# rpi_breakout.net
KiCad netlist of a schematic drawn in EAGLE
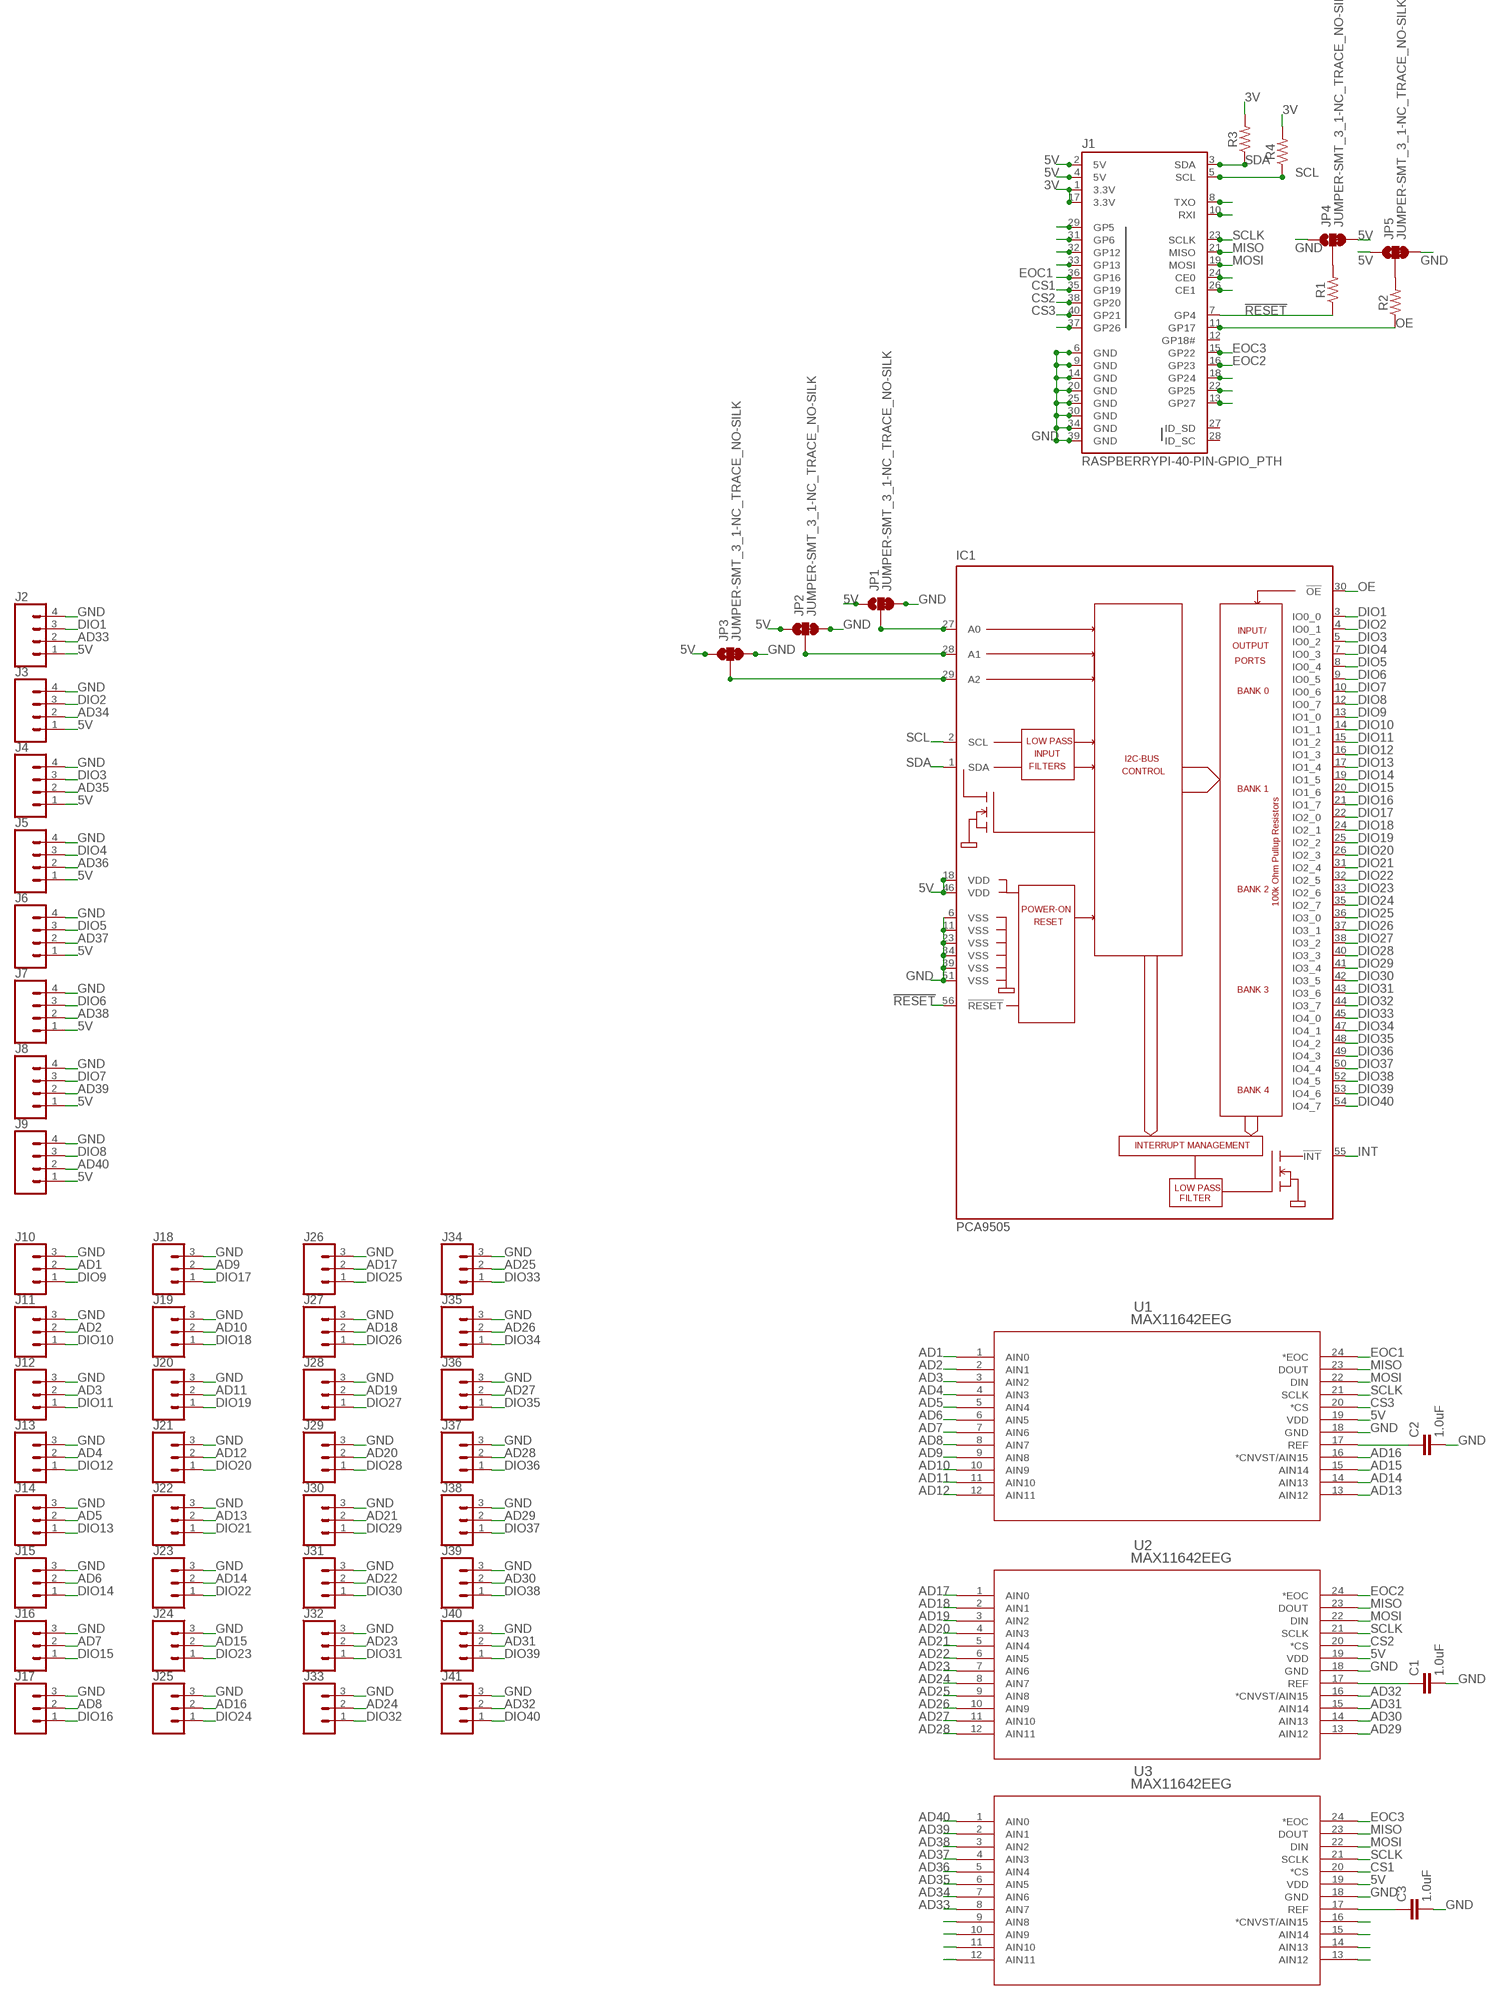
[diagram p0: schematic, sheet 1]

(export (version "E")
  (design (tool "Eeschema 10.0.6"))
  (components
    (comp (ref "C1")
      (value "1.0uF")
      (footprint "eagle-import:0805")
      (libsource (lib "eagle-import") (part "1.0UF-0805-25V-10%"))
    )
    (comp (ref "C2")
      (value "1.0uF")
      (footprint "eagle-import:0805")
      (libsource (lib "eagle-import") (part "1.0UF-0805-25V-10%"))
    )
    (comp (ref "C3")
      (value "1.0uF")
      (footprint "eagle-import:0805")
      (libsource (lib "eagle-import") (part "1.0UF-0805-25V-10%"))
    )
    (comp (ref "IC1")
      (value "PCA9505")
      (footprint "eagle-import:TSSOP56-6")
      (fields (field (name "MPN") "PCA9505DGG,118"))
      (libsource (lib "eagle-import") (part "PCA9505"))
    )
    (comp (ref "J1")
      (value "RASPBERRYPI-40-PIN-GPIO_PTH")
      (footprint "eagle-import:2X20_SHROUDED")
      (libsource (lib "eagle-import") (part "RASPBERRYPI-40-PIN-GPIO_PTH"))
    )
    (comp (ref "J2")
      (value "CONN_04JST-PTH")
      (footprint "eagle-import:JST-4-PTH")
      (libsource (lib "eagle-import") (part "CONN_04JST-PTH"))
    )
    (comp (ref "J3")
      (value "CONN_04JST-PTH")
      (footprint "eagle-import:JST-4-PTH")
      (libsource (lib "eagle-import") (part "CONN_04JST-PTH"))
    )
    (comp (ref "J4")
      (value "CONN_04JST-PTH")
      (footprint "eagle-import:JST-4-PTH")
      (libsource (lib "eagle-import") (part "CONN_04JST-PTH"))
    )
    (comp (ref "J5")
      (value "CONN_04JST-PTH")
      (footprint "eagle-import:JST-4-PTH")
      (libsource (lib "eagle-import") (part "CONN_04JST-PTH"))
    )
    (comp (ref "J6")
      (value "CONN_04JST-PTH")
      (footprint "eagle-import:JST-4-PTH")
      (libsource (lib "eagle-import") (part "CONN_04JST-PTH"))
    )
    (comp (ref "J7")
      (value "CONN_04JST-PTH")
      (footprint "eagle-import:JST-4-PTH")
      (libsource (lib "eagle-import") (part "CONN_04JST-PTH"))
    )
    (comp (ref "J8")
      (value "CONN_04JST-PTH")
      (footprint "eagle-import:JST-4-PTH")
      (libsource (lib "eagle-import") (part "CONN_04JST-PTH"))
    )
    (comp (ref "J9")
      (value "CONN_04JST-PTH")
      (footprint "eagle-import:JST-4-PTH")
      (libsource (lib "eagle-import") (part "CONN_04JST-PTH"))
    )
    (comp (ref "J10")
      (value "CONN_03JST-PTH")
      (footprint "eagle-import:JST-3-PTH")
      (libsource (lib "eagle-import") (part "CONN_03JST-PTH"))
    )
    (comp (ref "J11")
      (value "CONN_03JST-PTH")
      (footprint "eagle-import:JST-3-PTH")
      (libsource (lib "eagle-import") (part "CONN_03JST-PTH"))
    )
    (comp (ref "J12")
      (value "CONN_03JST-PTH")
      (footprint "eagle-import:JST-3-PTH")
      (libsource (lib "eagle-import") (part "CONN_03JST-PTH"))
    )
    (comp (ref "J13")
      (value "CONN_03JST-PTH")
      (footprint "eagle-import:JST-3-PTH")
      (libsource (lib "eagle-import") (part "CONN_03JST-PTH"))
    )
    (comp (ref "J14")
      (value "CONN_03JST-PTH")
      (footprint "eagle-import:JST-3-PTH")
      (libsource (lib "eagle-import") (part "CONN_03JST-PTH"))
    )
    (comp (ref "J15")
      (value "CONN_03JST-PTH")
      (footprint "eagle-import:JST-3-PTH")
      (libsource (lib "eagle-import") (part "CONN_03JST-PTH"))
    )
    (comp (ref "J16")
      (value "CONN_03JST-PTH")
      (footprint "eagle-import:JST-3-PTH")
      (libsource (lib "eagle-import") (part "CONN_03JST-PTH"))
    )
    (comp (ref "J17")
      (value "CONN_03JST-PTH")
      (footprint "eagle-import:JST-3-PTH")
      (libsource (lib "eagle-import") (part "CONN_03JST-PTH"))
    )
    (comp (ref "J18")
      (value "CONN_03JST-PTH")
      (footprint "eagle-import:JST-3-PTH")
      (libsource (lib "eagle-import") (part "CONN_03JST-PTH"))
    )
    (comp (ref "J19")
      (value "CONN_03JST-PTH")
      (footprint "eagle-import:JST-3-PTH")
      (libsource (lib "eagle-import") (part "CONN_03JST-PTH"))
    )
    (comp (ref "J20")
      (value "CONN_03JST-PTH")
      (footprint "eagle-import:JST-3-PTH")
      (libsource (lib "eagle-import") (part "CONN_03JST-PTH"))
    )
    (comp (ref "J21")
      (value "CONN_03JST-PTH")
      (footprint "eagle-import:JST-3-PTH")
      (libsource (lib "eagle-import") (part "CONN_03JST-PTH"))
    )
    (comp (ref "J22")
      (value "CONN_03JST-PTH")
      (footprint "eagle-import:JST-3-PTH")
      (libsource (lib "eagle-import") (part "CONN_03JST-PTH"))
    )
    (comp (ref "J23")
      (value "CONN_03JST-PTH")
      (footprint "eagle-import:JST-3-PTH")
      (libsource (lib "eagle-import") (part "CONN_03JST-PTH"))
    )
    (comp (ref "J24")
      (value "CONN_03JST-PTH")
      (footprint "eagle-import:JST-3-PTH")
      (libsource (lib "eagle-import") (part "CONN_03JST-PTH"))
    )
    (comp (ref "J25")
      (value "CONN_03JST-PTH")
      (footprint "eagle-import:JST-3-PTH")
      (libsource (lib "eagle-import") (part "CONN_03JST-PTH"))
    )
    (comp (ref "J26")
      (value "CONN_03JST-PTH")
      (footprint "eagle-import:JST-3-PTH")
      (libsource (lib "eagle-import") (part "CONN_03JST-PTH"))
    )
    (comp (ref "J27")
      (value "CONN_03JST-PTH")
      (footprint "eagle-import:JST-3-PTH")
      (libsource (lib "eagle-import") (part "CONN_03JST-PTH"))
    )
    (comp (ref "J28")
      (value "CONN_03JST-PTH")
      (footprint "eagle-import:JST-3-PTH")
      (libsource (lib "eagle-import") (part "CONN_03JST-PTH"))
    )
    (comp (ref "J29")
      (value "CONN_03JST-PTH")
      (footprint "eagle-import:JST-3-PTH")
      (libsource (lib "eagle-import") (part "CONN_03JST-PTH"))
    )
    (comp (ref "J30")
      (value "CONN_03JST-PTH")
      (footprint "eagle-import:JST-3-PTH")
      (libsource (lib "eagle-import") (part "CONN_03JST-PTH"))
    )
    (comp (ref "J31")
      (value "CONN_03JST-PTH")
      (footprint "eagle-import:JST-3-PTH")
      (libsource (lib "eagle-import") (part "CONN_03JST-PTH"))
    )
    (comp (ref "J32")
      (value "CONN_03JST-PTH")
      (footprint "eagle-import:JST-3-PTH")
      (libsource (lib "eagle-import") (part "CONN_03JST-PTH"))
    )
    (comp (ref "J33")
      (value "CONN_03JST-PTH")
      (footprint "eagle-import:JST-3-PTH")
      (libsource (lib "eagle-import") (part "CONN_03JST-PTH"))
    )
    (comp (ref "J34")
      (value "CONN_03JST-PTH")
      (footprint "eagle-import:JST-3-PTH")
      (libsource (lib "eagle-import") (part "CONN_03JST-PTH"))
    )
    (comp (ref "J35")
      (value "CONN_03JST-PTH")
      (footprint "eagle-import:JST-3-PTH")
      (libsource (lib "eagle-import") (part "CONN_03JST-PTH"))
    )
    (comp (ref "J36")
      (value "CONN_03JST-PTH")
      (footprint "eagle-import:JST-3-PTH")
      (libsource (lib "eagle-import") (part "CONN_03JST-PTH"))
    )
    (comp (ref "J37")
      (value "CONN_03JST-PTH")
      (footprint "eagle-import:JST-3-PTH")
      (libsource (lib "eagle-import") (part "CONN_03JST-PTH"))
    )
    (comp (ref "J38")
      (value "CONN_03JST-PTH")
      (footprint "eagle-import:JST-3-PTH")
      (libsource (lib "eagle-import") (part "CONN_03JST-PTH"))
    )
    (comp (ref "J39")
      (value "CONN_03JST-PTH")
      (footprint "eagle-import:JST-3-PTH")
      (libsource (lib "eagle-import") (part "CONN_03JST-PTH"))
    )
    (comp (ref "J40")
      (value "CONN_03JST-PTH")
      (footprint "eagle-import:JST-3-PTH")
      (libsource (lib "eagle-import") (part "CONN_03JST-PTH"))
    )
    (comp (ref "J41")
      (value "CONN_03JST-PTH")
      (footprint "eagle-import:JST-3-PTH")
      (libsource (lib "eagle-import") (part "CONN_03JST-PTH"))
    )
    (comp (ref "JP1")
      (value "JUMPER-SMT_3_1-NC_TRACE_NO-SILK")
      (footprint "eagle-import:SMT-JUMPER_3_1-NC_TRACE_NO-SILK")
      (libsource (lib "eagle-import") (part "JUMPER-SMT_3_1-NC_TRACE_NO-SILK"))
    )
    (comp (ref "JP2")
      (value "JUMPER-SMT_3_1-NC_TRACE_NO-SILK")
      (footprint "eagle-import:SMT-JUMPER_3_1-NC_TRACE_NO-SILK")
      (libsource (lib "eagle-import") (part "JUMPER-SMT_3_1-NC_TRACE_NO-SILK"))
    )
    (comp (ref "JP3")
      (value "JUMPER-SMT_3_1-NC_TRACE_NO-SILK")
      (footprint "eagle-import:SMT-JUMPER_3_1-NC_TRACE_NO-SILK")
      (libsource (lib "eagle-import") (part "JUMPER-SMT_3_1-NC_TRACE_NO-SILK"))
    )
    (comp (ref "JP4")
      (value "JUMPER-SMT_3_1-NC_TRACE_NO-SILK")
      (footprint "eagle-import:SMT-JUMPER_3_1-NC_TRACE_NO-SILK")
      (libsource (lib "eagle-import") (part "JUMPER-SMT_3_1-NC_TRACE_NO-SILK"))
    )
    (comp (ref "JP5")
      (value "JUMPER-SMT_3_1-NC_TRACE_NO-SILK")
      (footprint "eagle-import:SMT-JUMPER_3_1-NC_TRACE_NO-SILK")
      (libsource (lib "eagle-import") (part "JUMPER-SMT_3_1-NC_TRACE_NO-SILK"))
    )
    (comp (ref "R1")
      (value "RESISTOR0805")
      (footprint "eagle-import:0805")
      (libsource (lib "eagle-import") (part "RESISTOR0805"))
    )
    (comp (ref "R2")
      (value "RESISTOR0805")
      (footprint "eagle-import:0805")
      (libsource (lib "eagle-import") (part "RESISTOR0805"))
    )
    (comp (ref "R3")
      (value "RESISTOR0805")
      (footprint "eagle-import:0805")
      (libsource (lib "eagle-import") (part "RESISTOR0805"))
    )
    (comp (ref "R4")
      (value "RESISTOR0805")
      (footprint "eagle-import:0805")
      (libsource (lib "eagle-import") (part "RESISTOR0805"))
    )
    (comp (ref "U1")
      (value "MAX11642EEG")
      (footprint "eagle-import:21-0055H_24")
      (fields (field (name "MF") "Maxim Integrated") (field (name "MP") "MAX11642EEG+T"))
      (libsource (lib "eagle-import") (part "MAX11642EEG"))
    )
    (comp (ref "U2")
      (value "MAX11642EEG")
      (footprint "eagle-import:21-0055H_24")
      (fields (field (name "MF") "Maxim Integrated") (field (name "MP") "MAX11642EEG+T"))
      (libsource (lib "eagle-import") (part "MAX11642EEG"))
    )
    (comp (ref "U3")
      (value "MAX11642EEG")
      (footprint "eagle-import:21-0055H_24")
      (fields (field (name "MF") "Maxim Integrated") (field (name "MP") "MAX11642EEG+T"))
      (libsource (lib "eagle-import") (part "MAX11642EEG"))
    )
  )
  (nets
    (net (code "1") (name "/3V") (class "Default")
      (node (ref "J1") (pin "1") (pinfunction "3.3V_1") (pintype "power_in"))
      (node (ref "J1") (pin "17") (pinfunction "3.3V_17") (pintype "power_in"))
      (node (ref "R3") (pin "2") (pinfunction "2_2") (pintype "passive"))
      (node (ref "R4") (pin "2") (pinfunction "2_2") (pintype "passive"))
    )
    (net (code "2") (name "/5V") (class "Default")
      (node (ref "IC1") (pin "18") (pinfunction "VDD_18") (pintype "power_in"))
      (node (ref "IC1") (pin "46") (pinfunction "VDD_46") (pintype "power_in"))
      (node (ref "J1") (pin "2") (pinfunction "5V_2") (pintype "power_in"))
      (node (ref "J1") (pin "4") (pinfunction "5V_4") (pintype "power_in"))
      (node (ref "J2") (pin "1") (pinfunction "1_1") (pintype "passive"))
      (node (ref "J3") (pin "1") (pinfunction "1_1") (pintype "passive"))
      (node (ref "J4") (pin "1") (pinfunction "1_1") (pintype "passive"))
      (node (ref "J5") (pin "1") (pinfunction "1_1") (pintype "passive"))
      (node (ref "J6") (pin "1") (pinfunction "1_1") (pintype "passive"))
      (node (ref "J7") (pin "1") (pinfunction "1_1") (pintype "passive"))
      (node (ref "J8") (pin "1") (pinfunction "1_1") (pintype "passive"))
      (node (ref "J9") (pin "1") (pinfunction "1_1") (pintype "passive"))
      (node (ref "JP1") (pin "1") (pinfunction "1_1") (pintype "passive"))
      (node (ref "JP2") (pin "1") (pinfunction "1_1") (pintype "passive"))
      (node (ref "JP3") (pin "1") (pinfunction "1_1") (pintype "passive"))
      (node (ref "JP4") (pin "3") (pinfunction "3_3") (pintype "passive"))
      (node (ref "JP5") (pin "1") (pinfunction "1_1") (pintype "passive"))
      (node (ref "U1") (pin "19") (pinfunction "VDD_19") (pintype "power_in"))
      (node (ref "U2") (pin "19") (pinfunction "VDD_19") (pintype "power_in"))
      (node (ref "U3") (pin "19") (pinfunction "VDD_19") (pintype "power_in"))
    )
    (net (code "3") (name "/AD1") (class "Default")
      (node (ref "J10") (pin "2") (pinfunction "2_2") (pintype "passive"))
      (node (ref "U1") (pin "1") (pinfunction "AIN0_1") (pintype "input"))
    )
    (net (code "4") (name "/AD2") (class "Default")
      (node (ref "J11") (pin "2") (pinfunction "2_2") (pintype "passive"))
      (node (ref "U1") (pin "2") (pinfunction "AIN1_2") (pintype "input"))
    )
    (net (code "5") (name "/AD3") (class "Default")
      (node (ref "J12") (pin "2") (pinfunction "2_2") (pintype "passive"))
      (node (ref "U1") (pin "3") (pinfunction "AIN2_3") (pintype "input"))
    )
    (net (code "6") (name "/AD4") (class "Default")
      (node (ref "J13") (pin "2") (pinfunction "2_2") (pintype "passive"))
      (node (ref "U1") (pin "4") (pinfunction "AIN3_4") (pintype "input"))
    )
    (net (code "7") (name "/AD5") (class "Default")
      (node (ref "J14") (pin "2") (pinfunction "2_2") (pintype "passive"))
      (node (ref "U1") (pin "5") (pinfunction "AIN4_5") (pintype "input"))
    )
    (net (code "8") (name "/AD6") (class "Default")
      (node (ref "J15") (pin "2") (pinfunction "2_2") (pintype "passive"))
      (node (ref "U1") (pin "6") (pinfunction "AIN5_6") (pintype "input"))
    )
    (net (code "9") (name "/AD7") (class "Default")
      (node (ref "J16") (pin "2") (pinfunction "2_2") (pintype "passive"))
      (node (ref "U1") (pin "7") (pinfunction "AIN6_7") (pintype "input"))
    )
    (net (code "10") (name "/AD8") (class "Default")
      (node (ref "J17") (pin "2") (pinfunction "2_2") (pintype "passive"))
      (node (ref "U1") (pin "8") (pinfunction "AIN7_8") (pintype "input"))
    )
    (net (code "11") (name "/AD9") (class "Default")
      (node (ref "J18") (pin "2") (pinfunction "2_2") (pintype "passive"))
      (node (ref "U1") (pin "9") (pinfunction "AIN8_9") (pintype "input"))
    )
    (net (code "12") (name "/AD10") (class "Default")
      (node (ref "J19") (pin "2") (pinfunction "2_2") (pintype "passive"))
      (node (ref "U1") (pin "10") (pinfunction "AIN9_10") (pintype "input"))
    )
    (net (code "13") (name "/AD11") (class "Default")
      (node (ref "J20") (pin "2") (pinfunction "2_2") (pintype "passive"))
      (node (ref "U1") (pin "11") (pinfunction "AIN10_11") (pintype "input"))
    )
    (net (code "14") (name "/AD12") (class "Default")
      (node (ref "J21") (pin "2") (pinfunction "2_2") (pintype "passive"))
      (node (ref "U1") (pin "12") (pinfunction "AIN11_12") (pintype "input"))
    )
    (net (code "15") (name "/AD13") (class "Default")
      (node (ref "J22") (pin "2") (pinfunction "2_2") (pintype "passive"))
      (node (ref "U1") (pin "13") (pinfunction "AIN12_13") (pintype "input"))
    )
    (net (code "16") (name "/AD14") (class "Default")
      (node (ref "J23") (pin "2") (pinfunction "2_2") (pintype "passive"))
      (node (ref "U1") (pin "14") (pinfunction "AIN13_14") (pintype "input"))
    )
    (net (code "17") (name "/AD15") (class "Default")
      (node (ref "J24") (pin "2") (pinfunction "2_2") (pintype "passive"))
      (node (ref "U1") (pin "15") (pinfunction "AIN14_15") (pintype "input"))
    )
    (net (code "18") (name "/AD16") (class "Default")
      (node (ref "J25") (pin "2") (pinfunction "2_2") (pintype "passive"))
      (node (ref "U1") (pin "16") (pinfunction "*CNVST/AIN15_16") (pintype "passive"))
    )
    (net (code "19") (name "/AD17") (class "Default")
      (node (ref "J26") (pin "2") (pinfunction "2_2") (pintype "passive"))
      (node (ref "U2") (pin "1") (pinfunction "AIN0_1") (pintype "input"))
    )
    (net (code "20") (name "/AD18") (class "Default")
      (node (ref "J27") (pin "2") (pinfunction "2_2") (pintype "passive"))
      (node (ref "U2") (pin "2") (pinfunction "AIN1_2") (pintype "input"))
    )
    (net (code "21") (name "/AD19") (class "Default")
      (node (ref "J28") (pin "2") (pinfunction "2_2") (pintype "passive"))
      (node (ref "U2") (pin "3") (pinfunction "AIN2_3") (pintype "input"))
    )
    (net (code "22") (name "/AD20") (class "Default")
      (node (ref "J29") (pin "2") (pinfunction "2_2") (pintype "passive"))
      (node (ref "U2") (pin "4") (pinfunction "AIN3_4") (pintype "input"))
    )
    (net (code "23") (name "/AD21") (class "Default")
      (node (ref "J30") (pin "2") (pinfunction "2_2") (pintype "passive"))
      (node (ref "U2") (pin "5") (pinfunction "AIN4_5") (pintype "input"))
    )
    (net (code "24") (name "/AD22") (class "Default")
      (node (ref "J31") (pin "2") (pinfunction "2_2") (pintype "passive"))
      (node (ref "U2") (pin "6") (pinfunction "AIN5_6") (pintype "input"))
    )
    (net (code "25") (name "/AD23") (class "Default")
      (node (ref "J32") (pin "2") (pinfunction "2_2") (pintype "passive"))
      (node (ref "U2") (pin "7") (pinfunction "AIN6_7") (pintype "input"))
    )
    (net (code "26") (name "/AD24") (class "Default")
      (node (ref "J33") (pin "2") (pinfunction "2_2") (pintype "passive"))
      (node (ref "U2") (pin "8") (pinfunction "AIN7_8") (pintype "input"))
    )
    (net (code "27") (name "/AD25") (class "Default")
      (node (ref "J34") (pin "2") (pinfunction "2_2") (pintype "passive"))
      (node (ref "U2") (pin "9") (pinfunction "AIN8_9") (pintype "input"))
    )
    (net (code "28") (name "/AD26") (class "Default")
      (node (ref "J35") (pin "2") (pinfunction "2_2") (pintype "passive"))
      (node (ref "U2") (pin "10") (pinfunction "AIN9_10") (pintype "input"))
    )
    (net (code "29") (name "/AD27") (class "Default")
      (node (ref "J36") (pin "2") (pinfunction "2_2") (pintype "passive"))
      (node (ref "U2") (pin "11") (pinfunction "AIN10_11") (pintype "input"))
    )
    (net (code "30") (name "/AD28") (class "Default")
      (node (ref "J37") (pin "2") (pinfunction "2_2") (pintype "passive"))
      (node (ref "U2") (pin "12") (pinfunction "AIN11_12") (pintype "input"))
    )
    (net (code "31") (name "/AD29") (class "Default")
      (node (ref "J38") (pin "2") (pinfunction "2_2") (pintype "passive"))
      (node (ref "U2") (pin "13") (pinfunction "AIN12_13") (pintype "input"))
    )
    (net (code "32") (name "/AD30") (class "Default")
      (node (ref "J39") (pin "2") (pinfunction "2_2") (pintype "passive"))
      (node (ref "U2") (pin "14") (pinfunction "AIN13_14") (pintype "input"))
    )
    (net (code "33") (name "/AD31") (class "Default")
      (node (ref "J40") (pin "2") (pinfunction "2_2") (pintype "passive"))
      (node (ref "U2") (pin "15") (pinfunction "AIN14_15") (pintype "input"))
    )
    (net (code "34") (name "/AD32") (class "Default")
      (node (ref "J41") (pin "2") (pinfunction "2_2") (pintype "passive"))
      (node (ref "U2") (pin "16") (pinfunction "*CNVST/AIN15_16") (pintype "passive"))
    )
    (net (code "35") (name "/AD33") (class "Default")
      (node (ref "J2") (pin "2") (pinfunction "2_2") (pintype "passive"))
      (node (ref "U3") (pin "8") (pinfunction "AIN7_8") (pintype "input"))
    )
    (net (code "36") (name "/AD34") (class "Default")
      (node (ref "J3") (pin "2") (pinfunction "2_2") (pintype "passive"))
      (node (ref "U3") (pin "7") (pinfunction "AIN6_7") (pintype "input"))
    )
    (net (code "37") (name "/AD35") (class "Default")
      (node (ref "J4") (pin "2") (pinfunction "2_2") (pintype "passive"))
      (node (ref "U3") (pin "6") (pinfunction "AIN5_6") (pintype "input"))
    )
    (net (code "38") (name "/AD36") (class "Default")
      (node (ref "J5") (pin "2") (pinfunction "2_2") (pintype "passive"))
      (node (ref "U3") (pin "5") (pinfunction "AIN4_5") (pintype "input"))
    )
    (net (code "39") (name "/AD37") (class "Default")
      (node (ref "J6") (pin "2") (pinfunction "2_2") (pintype "passive"))
      (node (ref "U3") (pin "4") (pinfunction "AIN3_4") (pintype "input"))
    )
    (net (code "40") (name "/AD38") (class "Default")
      (node (ref "J7") (pin "2") (pinfunction "2_2") (pintype "passive"))
      (node (ref "U3") (pin "3") (pinfunction "AIN2_3") (pintype "input"))
    )
    (net (code "41") (name "/AD39") (class "Default")
      (node (ref "J8") (pin "2") (pinfunction "2_2") (pintype "passive"))
      (node (ref "U3") (pin "2") (pinfunction "AIN1_2") (pintype "input"))
    )
    (net (code "42") (name "/AD40") (class "Default")
      (node (ref "J9") (pin "2") (pinfunction "2_2") (pintype "passive"))
      (node (ref "U3") (pin "1") (pinfunction "AIN0_1") (pintype "input"))
    )
    (net (code "43") (name "/CS1") (class "Default")
      (node (ref "J1") (pin "35") (pinfunction "GP19_35") (pintype "bidirectional"))
      (node (ref "U3") (pin "20") (pinfunction "*CS_20") (pintype "passive"))
    )
    (net (code "44") (name "/CS2") (class "Default")
      (node (ref "J1") (pin "38") (pinfunction "GP20_38") (pintype "bidirectional"))
      (node (ref "U2") (pin "20") (pinfunction "*CS_20") (pintype "passive"))
    )
    (net (code "45") (name "/CS3") (class "Default")
      (node (ref "J1") (pin "40") (pinfunction "GP21_40") (pintype "bidirectional"))
      (node (ref "U1") (pin "20") (pinfunction "*CS_20") (pintype "passive"))
    )
    (net (code "46") (name "/DIO1") (class "Default")
      (node (ref "IC1") (pin "3") (pinfunction "IO0_0_3") (pintype "bidirectional"))
      (node (ref "J2") (pin "3") (pinfunction "3_3") (pintype "passive"))
    )
    (net (code "47") (name "/DIO2") (class "Default")
      (node (ref "IC1") (pin "4") (pinfunction "IO0_1_4") (pintype "bidirectional"))
      (node (ref "J3") (pin "3") (pinfunction "3_3") (pintype "passive"))
    )
    (net (code "48") (name "/DIO3") (class "Default")
      (node (ref "IC1") (pin "5") (pinfunction "IO0_2_5") (pintype "bidirectional"))
      (node (ref "J4") (pin "3") (pinfunction "3_3") (pintype "passive"))
    )
    (net (code "49") (name "/DIO4") (class "Default")
      (node (ref "IC1") (pin "7") (pinfunction "IO0_3_7") (pintype "bidirectional"))
      (node (ref "J5") (pin "3") (pinfunction "3_3") (pintype "passive"))
    )
    (net (code "50") (name "/DIO5") (class "Default")
      (node (ref "IC1") (pin "8") (pinfunction "IO0_4_8") (pintype "bidirectional"))
      (node (ref "J6") (pin "3") (pinfunction "3_3") (pintype "passive"))
    )
    (net (code "51") (name "/DIO6") (class "Default")
      (node (ref "IC1") (pin "9") (pinfunction "IO0_5_9") (pintype "bidirectional"))
      (node (ref "J7") (pin "3") (pinfunction "3_3") (pintype "passive"))
    )
    (net (code "52") (name "/DIO7") (class "Default")
      (node (ref "IC1") (pin "10") (pinfunction "IO0_6_10") (pintype "bidirectional"))
      (node (ref "J8") (pin "3") (pinfunction "3_3") (pintype "passive"))
    )
    (net (code "53") (name "/DIO8") (class "Default")
      (node (ref "IC1") (pin "12") (pinfunction "IO0_7_12") (pintype "bidirectional"))
      (node (ref "J9") (pin "3") (pinfunction "3_3") (pintype "passive"))
    )
    (net (code "54") (name "/DIO9") (class "Default")
      (node (ref "IC1") (pin "13") (pinfunction "IO1_0_13") (pintype "bidirectional"))
      (node (ref "J10") (pin "1") (pinfunction "1_1") (pintype "passive"))
    )
    (net (code "55") (name "/DIO10") (class "Default")
      (node (ref "IC1") (pin "14") (pinfunction "IO1_1_14") (pintype "bidirectional"))
      (node (ref "J11") (pin "1") (pinfunction "1_1") (pintype "passive"))
    )
    (net (code "56") (name "/DIO11") (class "Default")
      (node (ref "IC1") (pin "15") (pinfunction "IO1_2_15") (pintype "bidirectional"))
      (node (ref "J12") (pin "1") (pinfunction "1_1") (pintype "passive"))
    )
    (net (code "57") (name "/DIO12") (class "Default")
      (node (ref "IC1") (pin "16") (pinfunction "IO1_3_16") (pintype "bidirectional"))
      (node (ref "J13") (pin "1") (pinfunction "1_1") (pintype "passive"))
    )
    (net (code "58") (name "/DIO13") (class "Default")
      (node (ref "IC1") (pin "17") (pinfunction "IO1_4_17") (pintype "bidirectional"))
      (node (ref "J14") (pin "1") (pinfunction "1_1") (pintype "passive"))
    )
    (net (code "59") (name "/DIO14") (class "Default")
      (node (ref "IC1") (pin "19") (pinfunction "IO1_5_19") (pintype "bidirectional"))
      (node (ref "J15") (pin "1") (pinfunction "1_1") (pintype "passive"))
    )
    (net (code "60") (name "/DIO15") (class "Default")
      (node (ref "IC1") (pin "20") (pinfunction "IO1_6_20") (pintype "bidirectional"))
      (node (ref "J16") (pin "1") (pinfunction "1_1") (pintype "passive"))
    )
    (net (code "61") (name "/DIO16") (class "Default")
      (node (ref "IC1") (pin "21") (pinfunction "IO1_7_21") (pintype "bidirectional"))
      (node (ref "J17") (pin "1") (pinfunction "1_1") (pintype "passive"))
    )
    (net (code "62") (name "/DIO17") (class "Default")
      (node (ref "IC1") (pin "22") (pinfunction "IO2_0_22") (pintype "bidirectional"))
      (node (ref "J18") (pin "1") (pinfunction "1_1") (pintype "passive"))
    )
    (net (code "63") (name "/DIO18") (class "Default")
      (node (ref "IC1") (pin "24") (pinfunction "IO2_1_24") (pintype "bidirectional"))
      (node (ref "J19") (pin "1") (pinfunction "1_1") (pintype "passive"))
    )
    (net (code "64") (name "/DIO19") (class "Default")
      (node (ref "IC1") (pin "25") (pinfunction "IO2_2_25") (pintype "bidirectional"))
      (node (ref "J20") (pin "1") (pinfunction "1_1") (pintype "passive"))
    )
    (net (code "65") (name "/DIO20") (class "Default")
      (node (ref "IC1") (pin "26") (pinfunction "IO2_3_26") (pintype "bidirectional"))
      (node (ref "J21") (pin "1") (pinfunction "1_1") (pintype "passive"))
    )
    (net (code "66") (name "/DIO21") (class "Default")
      (node (ref "IC1") (pin "31") (pinfunction "IO2_4_31") (pintype "bidirectional"))
      (node (ref "J22") (pin "1") (pinfunction "1_1") (pintype "passive"))
    )
    (net (code "67") (name "/DIO22") (class "Default")
      (node (ref "IC1") (pin "32") (pinfunction "IO2_5_32") (pintype "bidirectional"))
      (node (ref "J23") (pin "1") (pinfunction "1_1") (pintype "passive"))
    )
    (net (code "68") (name "/DIO23") (class "Default")
      (node (ref "IC1") (pin "33") (pinfunction "IO2_6_33") (pintype "bidirectional"))
      (node (ref "J24") (pin "1") (pinfunction "1_1") (pintype "passive"))
    )
    (net (code "69") (name "/DIO24") (class "Default")
      (node (ref "IC1") (pin "35") (pinfunction "IO2_7_35") (pintype "bidirectional"))
      (node (ref "J25") (pin "1") (pinfunction "1_1") (pintype "passive"))
    )
    (net (code "70") (name "/DIO25") (class "Default")
      (node (ref "IC1") (pin "36") (pinfunction "IO3_0_36") (pintype "bidirectional"))
      (node (ref "J26") (pin "1") (pinfunction "1_1") (pintype "passive"))
    )
    (net (code "71") (name "/DIO26") (class "Default")
      (node (ref "IC1") (pin "37") (pinfunction "IO3_1_37") (pintype "bidirectional"))
      (node (ref "J27") (pin "1") (pinfunction "1_1") (pintype "passive"))
    )
    (net (code "72") (name "/DIO27") (class "Default")
      (node (ref "IC1") (pin "38") (pinfunction "IO3_2_38") (pintype "bidirectional"))
      (node (ref "J28") (pin "1") (pinfunction "1_1") (pintype "passive"))
    )
    (net (code "73") (name "/DIO28") (class "Default")
      (node (ref "IC1") (pin "40") (pinfunction "IO3_3_40") (pintype "bidirectional"))
      (node (ref "J29") (pin "1") (pinfunction "1_1") (pintype "passive"))
    )
    (net (code "74") (name "/DIO29") (class "Default")
      (node (ref "IC1") (pin "41") (pinfunction "IO3_4_41") (pintype "bidirectional"))
      (node (ref "J30") (pin "1") (pinfunction "1_1") (pintype "passive"))
    )
    (net (code "75") (name "/DIO30") (class "Default")
      (node (ref "IC1") (pin "42") (pinfunction "IO3_5_42") (pintype "bidirectional"))
      (node (ref "J31") (pin "1") (pinfunction "1_1") (pintype "passive"))
    )
    (net (code "76") (name "/DIO31") (class "Default")
      (node (ref "IC1") (pin "43") (pinfunction "IO3_6_43") (pintype "bidirectional"))
      (node (ref "J32") (pin "1") (pinfunction "1_1") (pintype "passive"))
    )
    (net (code "77") (name "/DIO32") (class "Default")
      (node (ref "IC1") (pin "44") (pinfunction "IO3_7_44") (pintype "bidirectional"))
      (node (ref "J33") (pin "1") (pinfunction "1_1") (pintype "passive"))
    )
    (net (code "78") (name "/DIO33") (class "Default")
      (node (ref "IC1") (pin "45") (pinfunction "IO4_0_45") (pintype "bidirectional"))
      (node (ref "J34") (pin "1") (pinfunction "1_1") (pintype "passive"))
    )
    (net (code "79") (name "/DIO34") (class "Default")
      (node (ref "IC1") (pin "47") (pinfunction "IO4_1_47") (pintype "bidirectional"))
      (node (ref "J35") (pin "1") (pinfunction "1_1") (pintype "passive"))
    )
    (net (code "80") (name "/DIO35") (class "Default")
      (node (ref "IC1") (pin "48") (pinfunction "IO4_2_48") (pintype "bidirectional"))
      (node (ref "J36") (pin "1") (pinfunction "1_1") (pintype "passive"))
    )
    (net (code "81") (name "/DIO36") (class "Default")
      (node (ref "IC1") (pin "49") (pinfunction "IO4_3_49") (pintype "bidirectional"))
      (node (ref "J37") (pin "1") (pinfunction "1_1") (pintype "passive"))
    )
    (net (code "82") (name "/DIO37") (class "Default")
      (node (ref "IC1") (pin "50") (pinfunction "IO4_4_50") (pintype "bidirectional"))
      (node (ref "J38") (pin "1") (pinfunction "1_1") (pintype "passive"))
    )
    (net (code "83") (name "/DIO38") (class "Default")
      (node (ref "IC1") (pin "52") (pinfunction "IO4_5_52") (pintype "bidirectional"))
      (node (ref "J39") (pin "1") (pinfunction "1_1") (pintype "passive"))
    )
    (net (code "84") (name "/DIO39") (class "Default")
      (node (ref "IC1") (pin "53") (pinfunction "IO4_6_53") (pintype "bidirectional"))
      (node (ref "J40") (pin "1") (pinfunction "1_1") (pintype "passive"))
    )
    (net (code "85") (name "/DIO40") (class "Default")
      (node (ref "IC1") (pin "54") (pinfunction "IO4_7_54") (pintype "bidirectional"))
      (node (ref "J41") (pin "1") (pinfunction "1_1") (pintype "passive"))
    )
    (net (code "86") (name "/EOC1") (class "Default")
      (node (ref "J1") (pin "36") (pinfunction "GP16_36") (pintype "bidirectional"))
      (node (ref "U1") (pin "24") (pinfunction "*EOC_24") (pintype "passive"))
    )
    (net (code "87") (name "/EOC2") (class "Default")
      (node (ref "J1") (pin "16") (pinfunction "GP23_16") (pintype "bidirectional"))
      (node (ref "U2") (pin "24") (pinfunction "*EOC_24") (pintype "passive"))
    )
    (net (code "88") (name "/EOC3") (class "Default")
      (node (ref "J1") (pin "15") (pinfunction "GP22_15") (pintype "bidirectional"))
      (node (ref "U3") (pin "24") (pinfunction "*EOC_24") (pintype "passive"))
    )
    (net (code "89") (name "/GND") (class "Default")
      (node (ref "C1") (pin "2") (pinfunction "2_2") (pintype "passive"))
      (node (ref "C2") (pin "2") (pinfunction "2_2") (pintype "passive"))
      (node (ref "C3") (pin "2") (pinfunction "2_2") (pintype "passive"))
      (node (ref "IC1") (pin "11") (pinfunction "VSS_11") (pintype "power_in"))
      (node (ref "IC1") (pin "23") (pinfunction "VSS_23") (pintype "power_in"))
      (node (ref "IC1") (pin "34") (pinfunction "VSS_34") (pintype "power_in"))
      (node (ref "IC1") (pin "39") (pinfunction "VSS_39") (pintype "power_in"))
      (node (ref "IC1") (pin "51") (pinfunction "VSS_51") (pintype "power_in"))
      (node (ref "IC1") (pin "6") (pinfunction "VSS_6") (pintype "power_in"))
      (node (ref "J1") (pin "14") (pinfunction "GND_14") (pintype "power_in"))
      (node (ref "J1") (pin "20") (pinfunction "GND_20") (pintype "power_in"))
      (node (ref "J1") (pin "25") (pinfunction "GND_25") (pintype "power_in"))
      (node (ref "J1") (pin "30") (pinfunction "GND_30") (pintype "power_in"))
      (node (ref "J1") (pin "34") (pinfunction "GND_34") (pintype "power_in"))
      (node (ref "J1") (pin "39") (pinfunction "GND_39") (pintype "power_in"))
      (node (ref "J1") (pin "6") (pinfunction "GND_6") (pintype "power_in"))
      (node (ref "J1") (pin "9") (pinfunction "GND_9") (pintype "power_in"))
      (node (ref "J10") (pin "3") (pinfunction "3_3") (pintype "passive"))
      (node (ref "J11") (pin "3") (pinfunction "3_3") (pintype "passive"))
      (node (ref "J12") (pin "3") (pinfunction "3_3") (pintype "passive"))
      (node (ref "J13") (pin "3") (pinfunction "3_3") (pintype "passive"))
      (node (ref "J14") (pin "3") (pinfunction "3_3") (pintype "passive"))
      (node (ref "J15") (pin "3") (pinfunction "3_3") (pintype "passive"))
      (node (ref "J16") (pin "3") (pinfunction "3_3") (pintype "passive"))
      (node (ref "J17") (pin "3") (pinfunction "3_3") (pintype "passive"))
      (node (ref "J18") (pin "3") (pinfunction "3_3") (pintype "passive"))
      (node (ref "J19") (pin "3") (pinfunction "3_3") (pintype "passive"))
      (node (ref "J2") (pin "4") (pinfunction "4_4") (pintype "passive"))
      (node (ref "J20") (pin "3") (pinfunction "3_3") (pintype "passive"))
      (node (ref "J21") (pin "3") (pinfunction "3_3") (pintype "passive"))
      (node (ref "J22") (pin "3") (pinfunction "3_3") (pintype "passive"))
      (node (ref "J23") (pin "3") (pinfunction "3_3") (pintype "passive"))
      (node (ref "J24") (pin "3") (pinfunction "3_3") (pintype "passive"))
      (node (ref "J25") (pin "3") (pinfunction "3_3") (pintype "passive"))
      (node (ref "J26") (pin "3") (pinfunction "3_3") (pintype "passive"))
      (node (ref "J27") (pin "3") (pinfunction "3_3") (pintype "passive"))
      (node (ref "J28") (pin "3") (pinfunction "3_3") (pintype "passive"))
      (node (ref "J29") (pin "3") (pinfunction "3_3") (pintype "passive"))
      (node (ref "J3") (pin "4") (pinfunction "4_4") (pintype "passive"))
      (node (ref "J30") (pin "3") (pinfunction "3_3") (pintype "passive"))
      (node (ref "J31") (pin "3") (pinfunction "3_3") (pintype "passive"))
      (node (ref "J32") (pin "3") (pinfunction "3_3") (pintype "passive"))
      (node (ref "J33") (pin "3") (pinfunction "3_3") (pintype "passive"))
      (node (ref "J34") (pin "3") (pinfunction "3_3") (pintype "passive"))
      (node (ref "J35") (pin "3") (pinfunction "3_3") (pintype "passive"))
      (node (ref "J36") (pin "3") (pinfunction "3_3") (pintype "passive"))
      (node (ref "J37") (pin "3") (pinfunction "3_3") (pintype "passive"))
      (node (ref "J38") (pin "3") (pinfunction "3_3") (pintype "passive"))
      (node (ref "J39") (pin "3") (pinfunction "3_3") (pintype "passive"))
      (node (ref "J4") (pin "4") (pinfunction "4_4") (pintype "passive"))
      (node (ref "J40") (pin "3") (pinfunction "3_3") (pintype "passive"))
      (node (ref "J41") (pin "3") (pinfunction "3_3") (pintype "passive"))
      (node (ref "J5") (pin "4") (pinfunction "4_4") (pintype "passive"))
      (node (ref "J6") (pin "4") (pinfunction "4_4") (pintype "passive"))
      (node (ref "J7") (pin "4") (pinfunction "4_4") (pintype "passive"))
      (node (ref "J8") (pin "4") (pinfunction "4_4") (pintype "passive"))
      (node (ref "J9") (pin "4") (pinfunction "4_4") (pintype "passive"))
      (node (ref "JP1") (pin "3") (pinfunction "3_3") (pintype "passive"))
      (node (ref "JP2") (pin "3") (pinfunction "3_3") (pintype "passive"))
      (node (ref "JP3") (pin "3") (pinfunction "3_3") (pintype "passive"))
      (node (ref "JP4") (pin "1") (pinfunction "1_1") (pintype "passive"))
      (node (ref "JP5") (pin "3") (pinfunction "3_3") (pintype "passive"))
      (node (ref "U1") (pin "18") (pinfunction "GND_18") (pintype "power_in"))
      (node (ref "U2") (pin "18") (pinfunction "GND_18") (pintype "power_in"))
      (node (ref "U3") (pin "18") (pinfunction "GND_18") (pintype "power_in"))
    )
    (net (code "90") (name "/INT") (class "Default")
      (node (ref "IC1") (pin "55") (pinfunction "~{INT}_55") (pintype "input"))
    )
    (net (code "91") (name "/MISO") (class "Default")
      (node (ref "J1") (pin "21") (pinfunction "MISO_21") (pintype "input"))
      (node (ref "U1") (pin "23") (pinfunction "DOUT_23") (pintype "output"))
      (node (ref "U2") (pin "23") (pinfunction "DOUT_23") (pintype "output"))
      (node (ref "U3") (pin "23") (pinfunction "DOUT_23") (pintype "output"))
    )
    (net (code "92") (name "/MOSI") (class "Default")
      (node (ref "J1") (pin "19") (pinfunction "MOSI_19") (pintype "output"))
      (node (ref "U1") (pin "22") (pinfunction "DIN_22") (pintype "input"))
      (node (ref "U2") (pin "22") (pinfunction "DIN_22") (pintype "input"))
      (node (ref "U3") (pin "22") (pinfunction "DIN_22") (pintype "input"))
    )
    (net (code "93") (name "/OE") (class "Default")
      (node (ref "IC1") (pin "30") (pinfunction "~{OE}_30") (pintype "input"))
      (node (ref "J1") (pin "11") (pinfunction "GP17_11") (pintype "bidirectional"))
      (node (ref "R2") (pin "1") (pinfunction "1_1") (pintype "passive"))
    )
    (net (code "94") (name "/SCL") (class "Default")
      (node (ref "IC1") (pin "2") (pinfunction "SCL_2") (pintype "input"))
      (node (ref "J1") (pin "5") (pinfunction "SCL_5") (pintype "bidirectional"))
      (node (ref "R4") (pin "1") (pinfunction "1_1") (pintype "passive"))
    )
    (net (code "95") (name "/SCLK") (class "Default")
      (node (ref "J1") (pin "23") (pinfunction "SCLK_23") (pintype "output"))
      (node (ref "U1") (pin "21") (pinfunction "SCLK_21") (pintype "passive"))
      (node (ref "U2") (pin "21") (pinfunction "SCLK_21") (pintype "passive"))
      (node (ref "U3") (pin "21") (pinfunction "SCLK_21") (pintype "passive"))
    )
    (net (code "96") (name "/SDA") (class "Default")
      (node (ref "IC1") (pin "1") (pinfunction "SDA_1") (pintype "bidirectional"))
      (node (ref "J1") (pin "3") (pinfunction "SDA_3") (pintype "bidirectional"))
      (node (ref "R3") (pin "1") (pinfunction "1_1") (pintype "passive"))
    )
    (net (code "97") (name "/~{RESET}") (class "Default")
      (node (ref "IC1") (pin "56") (pinfunction "~{RESET}_56") (pintype "input"))
      (node (ref "J1") (pin "7") (pinfunction "GP4_7") (pintype "bidirectional"))
      (node (ref "R1") (pin "1") (pinfunction "1_1") (pintype "passive"))
    )
    (net (code "98") (name "Net-(IC1-A0)") (class "Default")
      (node (ref "IC1") (pin "27") (pinfunction "A0_27") (pintype "input"))
      (node (ref "JP1") (pin "2") (pinfunction "2_2") (pintype "passive"))
    )
    (net (code "99") (name "Net-(IC1-A1)") (class "Default")
      (node (ref "IC1") (pin "28") (pinfunction "A1_28") (pintype "input"))
      (node (ref "JP2") (pin "2") (pinfunction "2_2") (pintype "passive"))
    )
    (net (code "100") (name "Net-(IC1-A2)") (class "Default")
      (node (ref "IC1") (pin "29") (pinfunction "A2_29") (pintype "input"))
      (node (ref "JP3") (pin "2") (pinfunction "2_2") (pintype "passive"))
    )
    (net (code "101") (name "Net-(JP4-Pad2)") (class "Default")
      (node (ref "JP4") (pin "2") (pinfunction "2_2") (pintype "passive"))
      (node (ref "R1") (pin "2") (pinfunction "2_2") (pintype "passive"))
    )
    (net (code "102") (name "Net-(JP5-Pad2)") (class "Default")
      (node (ref "JP5") (pin "2") (pinfunction "2_2") (pintype "passive"))
      (node (ref "R2") (pin "2") (pinfunction "2_2") (pintype "passive"))
    )
    (net (code "103") (name "Net-(U1-REF)") (class "Default")
      (node (ref "C2") (pin "1") (pinfunction "1_1") (pintype "passive"))
      (node (ref "U1") (pin "17") (pinfunction "REF_17") (pintype "passive"))
    )
    (net (code "104") (name "Net-(U2-REF)") (class "Default")
      (node (ref "C1") (pin "1") (pinfunction "1_1") (pintype "passive"))
      (node (ref "U2") (pin "17") (pinfunction "REF_17") (pintype "passive"))
    )
    (net (code "105") (name "Net-(U3-REF)") (class "Default")
      (node (ref "C3") (pin "1") (pinfunction "1_1") (pintype "passive"))
      (node (ref "U3") (pin "17") (pinfunction "REF_17") (pintype "passive"))
    )
    (net (code "106") (name "unconnected-(J1-CE0-Pad24)") (class "Default")
      (node (ref "J1") (pin "24") (pinfunction "CE0_24") (pintype "output"))
    )
    (net (code "107") (name "unconnected-(J1-CE1-Pad26)") (class "Default")
      (node (ref "J1") (pin "26") (pinfunction "CE1_26") (pintype "output"))
    )
    (net (code "108") (name "unconnected-(J1-GP5-Pad29)") (class "Default")
      (node (ref "J1") (pin "29") (pinfunction "GP5_29") (pintype "bidirectional"))
    )
    (net (code "109") (name "unconnected-(J1-GP6-Pad31)") (class "Default")
      (node (ref "J1") (pin "31") (pinfunction "GP6_31") (pintype "bidirectional"))
    )
    (net (code "110") (name "unconnected-(J1-GP12-Pad32)") (class "Default")
      (node (ref "J1") (pin "32") (pinfunction "GP12_32") (pintype "bidirectional"))
    )
    (net (code "111") (name "unconnected-(J1-GP13-Pad33)") (class "Default")
      (node (ref "J1") (pin "33") (pinfunction "GP13_33") (pintype "bidirectional"))
    )
    (net (code "112") (name "unconnected-(J1-GP18#-Pad12)") (class "Default")
      (node (ref "J1") (pin "12") (pinfunction "GP18#_12") (pintype "bidirectional"))
    )
    (net (code "113") (name "unconnected-(J1-GP24-Pad18)") (class "Default")
      (node (ref "J1") (pin "18") (pinfunction "GP24_18") (pintype "bidirectional"))
    )
    (net (code "114") (name "unconnected-(J1-GP25-Pad22)") (class "Default")
      (node (ref "J1") (pin "22") (pinfunction "GP25_22") (pintype "bidirectional"))
    )
    (net (code "115") (name "unconnected-(J1-GP26-Pad37)") (class "Default")
      (node (ref "J1") (pin "37") (pinfunction "GP26_37") (pintype "bidirectional"))
    )
    (net (code "116") (name "unconnected-(J1-GP27-Pad13)") (class "Default")
      (node (ref "J1") (pin "13") (pinfunction "GP27_13") (pintype "bidirectional"))
    )
    (net (code "117") (name "unconnected-(J1-ID_SC-Pad28)") (class "Default")
      (node (ref "J1") (pin "28") (pinfunction "ID_SC_28") (pintype "bidirectional"))
    )
    (net (code "118") (name "unconnected-(J1-ID_SD-Pad27)") (class "Default")
      (node (ref "J1") (pin "27") (pinfunction "ID_SD_27") (pintype "bidirectional"))
    )
    (net (code "119") (name "unconnected-(J1-RXI-Pad10)") (class "Default")
      (node (ref "J1") (pin "10") (pinfunction "RXI_10") (pintype "input"))
    )
    (net (code "120") (name "unconnected-(J1-TXO-Pad8)") (class "Default")
      (node (ref "J1") (pin "8") (pinfunction "TXO_8") (pintype "output"))
    )
    (net (code "121") (name "unconnected-(U3-*CNVST{slash}AIN15-Pad16)") (class "Default")
      (node (ref "U3") (pin "16") (pinfunction "*CNVST/AIN15_16") (pintype "passive"))
    )
    (net (code "122") (name "unconnected-(U3-AIN8-Pad9)") (class "Default")
      (node (ref "U3") (pin "9") (pinfunction "AIN8_9") (pintype "input"))
    )
    (net (code "123") (name "unconnected-(U3-AIN9-Pad10)") (class "Default")
      (node (ref "U3") (pin "10") (pinfunction "AIN9_10") (pintype "input"))
    )
    (net (code "124") (name "unconnected-(U3-AIN10-Pad11)") (class "Default")
      (node (ref "U3") (pin "11") (pinfunction "AIN10_11") (pintype "input"))
    )
    (net (code "125") (name "unconnected-(U3-AIN11-Pad12)") (class "Default")
      (node (ref "U3") (pin "12") (pinfunction "AIN11_12") (pintype "input"))
    )
    (net (code "126") (name "unconnected-(U3-AIN12-Pad13)") (class "Default")
      (node (ref "U3") (pin "13") (pinfunction "AIN12_13") (pintype "input"))
    )
    (net (code "127") (name "unconnected-(U3-AIN13-Pad14)") (class "Default")
      (node (ref "U3") (pin "14") (pinfunction "AIN13_14") (pintype "input"))
    )
    (net (code "128") (name "unconnected-(U3-AIN14-Pad15)") (class "Default")
      (node (ref "U3") (pin "15") (pinfunction "AIN14_15") (pintype "input"))
    )
  )
)
